# BACKUP_POWER.net
KiCad netlist of a schematic drawn in Altium Designer
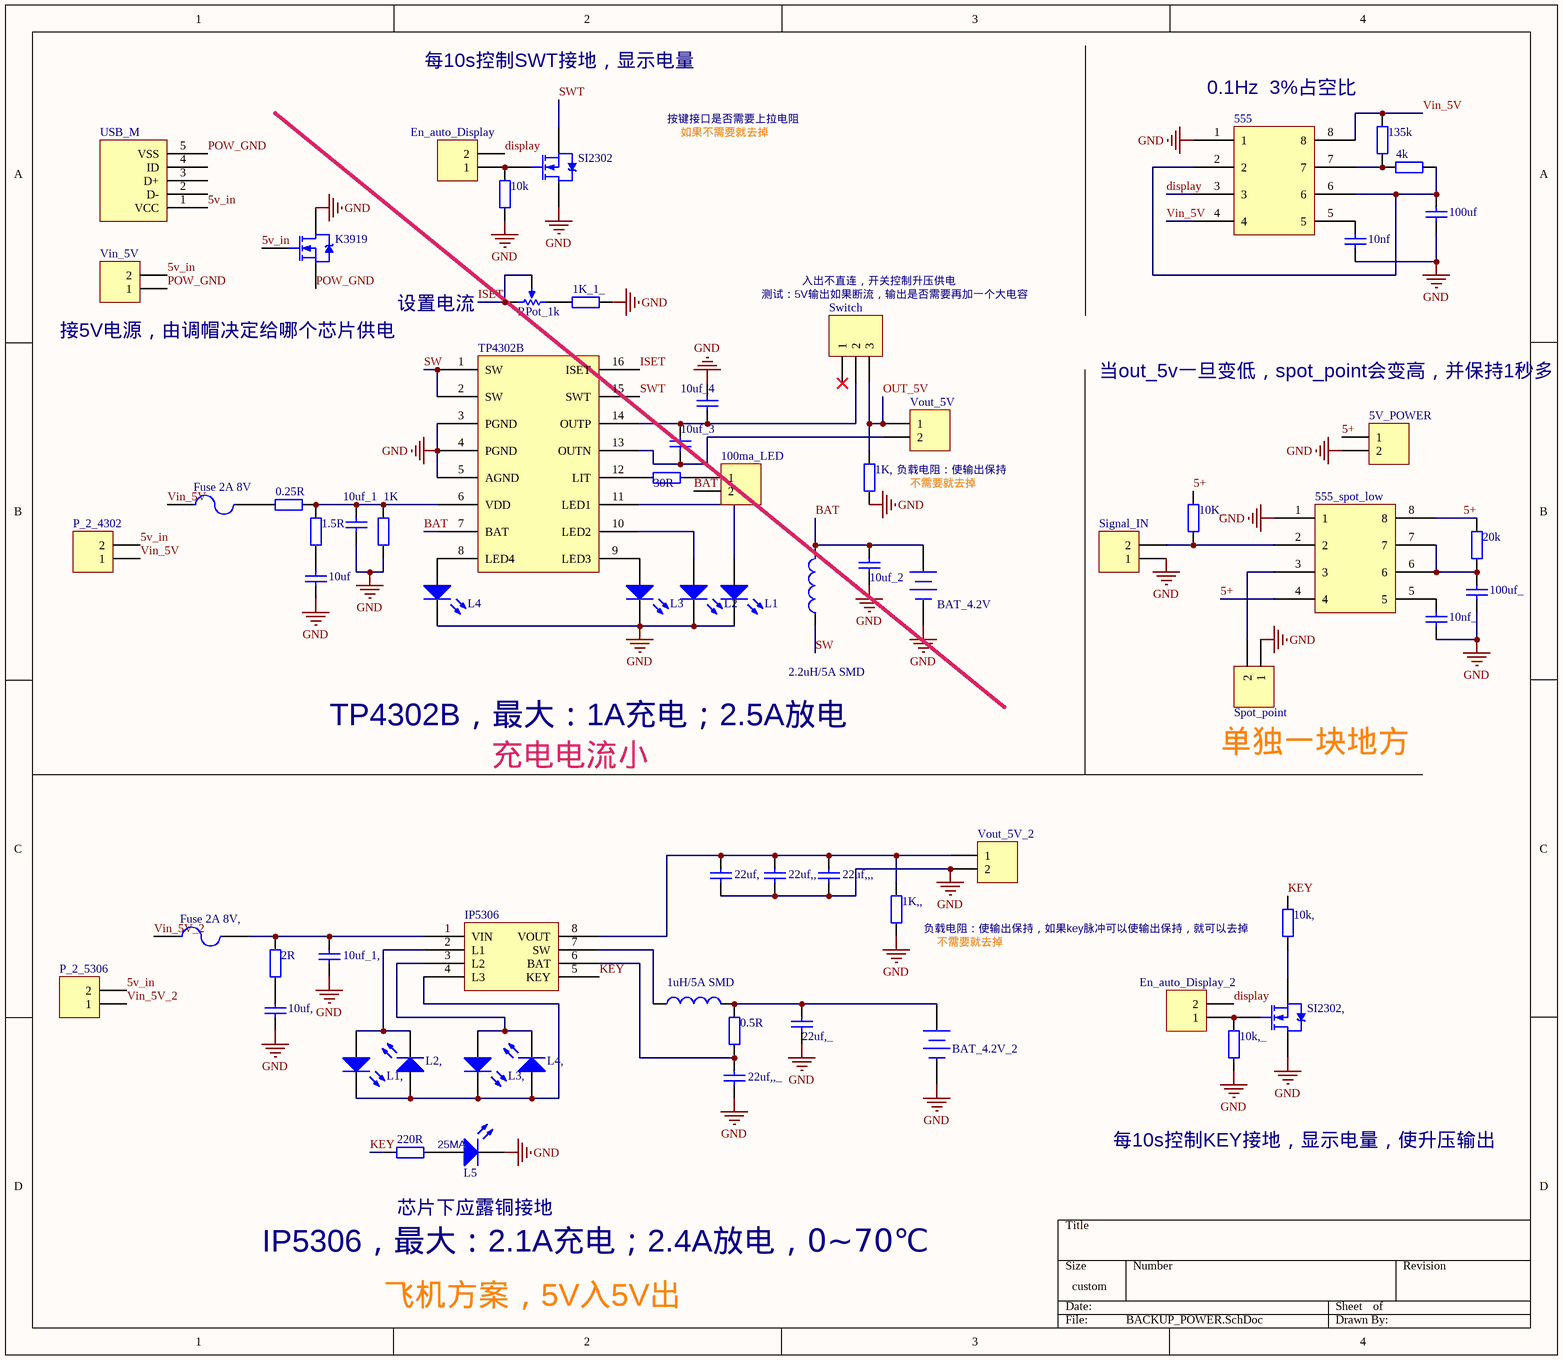
[diagram p0: BACKUP_POWER.SchDoc]

(export (version "E")
  (design (tool "Eeschema 10.0.6"))
  (components
    (comp (ref "0.5R")
      (value "Res2")
      (footprint "0805A")
      (description "Resistor")
      (fields (field (name "PUBLISHER") "Altium Limited"))
      (libsource (lib "") (part "Res2_2"))
    )
    (comp (ref "0.25R")
      (value "Res2")
      (footprint "1206")
      (description "Resistor")
      (fields (field (name "PUBLISHER") "Altium Limited"))
      (libsource (lib "Miscellaneous Devices") (part "Res2"))
    )
    (comp (ref "1.5R")
      (value "Res2")
      (footprint "0805A")
      (description "Resistor")
      (fields (field (name "PUBLISHER") "Altium Limited"))
      (libsource (lib "") (part "Res2_1"))
    )
    (comp (ref "1K")
      (value "Res2")
      (footprint "0805A")
      (description "Resistor")
      (fields (field (name "PUBLISHER") "Altium Limited"))
      (libsource (lib "") (part "Res2_1"))
    )
    (comp (ref "1K,")
      (value "Res2")
      (footprint "0805A")
      (description "Resistor")
      (fields (field (name "PUBLISHER") "Altium Limited"))
      (libsource (lib "") (part "Res2_1"))
    )
    (comp (ref "1K,,")
      (value "Res2")
      (footprint "0805A")
      (description "Resistor")
      (fields (field (name "PUBLISHER") "Altium Limited"))
      (libsource (lib "") (part "Res2_1"))
    )
    (comp (ref "1K_1_")
      (value "Res2")
      (footprint "0805A")
      (description "Resistor")
      (fields (field (name "PUBLISHER") "Altium Limited"))
      (libsource (lib "Miscellaneous Devices") (part "Res2"))
    )
    (comp (ref "1uH/5A SMD")
      (value "Inductor")
      (footprint "6 X 6-L")
      (fields (field (name "PUBLISHER") "Altium Limited"))
      (libsource (lib "Miscellaneous Devices") (part "Inductor"))
    )
    (comp (ref "2.2uH/5A SMD")
      (value "Inductor")
      (footprint "6 X 6-L")
      (fields (field (name "PUBLISHER") "Altium Limited"))
      (libsource (lib "Miscellaneous Devices") (part "Inductor"))
    )
    (comp (ref "2R")
      (value "Res2")
      (footprint "0805A")
      (description "Resistor")
      (fields (field (name "PUBLISHER") "Altium Limited"))
      (libsource (lib "") (part "Res2_1"))
    )
    (comp (ref "4k")
      (value "Res2")
      (footprint "0805A")
      (description "Resistor")
      (fields (field (name "PUBLISHER") "Altium Limited"))
      (libsource (lib "Miscellaneous Devices") (part "Res2"))
    )
    (comp (ref "5V_POWER")
      (value "Header 2")
      (footprint "HDR1X2")
      (description "Header, 2-Pin")
      (fields (field (name "PUBLISHER") "Altium Limited"))
      (libsource (lib "") (part "Header 2_1"))
    )
    (comp (ref "10k")
      (value "Res2")
      (footprint "0805A")
      (description "Resistor")
      (fields (field (name "PUBLISHER") "Altium Limited"))
      (libsource (lib "") (part "Res2_2"))
    )
    (comp (ref "10k,")
      (value "Res2")
      (footprint "0805A")
      (description "Resistor")
      (fields (field (name "PUBLISHER") "Altium Limited"))
      (libsource (lib "") (part "Res2_2"))
    )
    (comp (ref "10k,_")
      (value "Res2")
      (footprint "0805A")
      (description "Resistor")
      (fields (field (name "PUBLISHER") "Altium Limited"))
      (libsource (lib "") (part "Res2_2"))
    )
    (comp (ref "10K_")
      (value "Res2")
      (footprint "0805A")
      (description "Resistor")
      (fields (field (name "PUBLISHER") "Altium Limited"))
      (libsource (lib "") (part "Res2_1"))
    )
    (comp (ref "10nf")
      (value "Cap")
      (footprint "C-RAD-0805")
      (description "Capacitor")
      (fields (field (name "PUBLISHER") "Altium Limited"))
      (libsource (lib "Miscellaneous Devices") (part "Cap"))
    )
    (comp (ref "10nf_")
      (value "Cap")
      (footprint "C-RAD-0805")
      (description "Capacitor")
      (fields (field (name "PUBLISHER") "Altium Limited"))
      (libsource (lib "Miscellaneous Devices") (part "Cap"))
    )
    (comp (ref "10uf")
      (value "Cap")
      (footprint "C-RAD-0805")
      (description "Capacitor")
      (fields (field (name "PUBLISHER") "Altium Limited"))
      (libsource (lib "Miscellaneous Devices") (part "Cap"))
    )
    (comp (ref "10uf,")
      (value "Cap")
      (footprint "C-RAD-0805")
      (description "Capacitor")
      (fields (field (name "PUBLISHER") "Altium Limited"))
      (libsource (lib "Miscellaneous Devices") (part "Cap"))
    )
    (comp (ref "10uf_1")
      (value "Cap")
      (footprint "C-RAD-0805")
      (description "Capacitor")
      (fields (field (name "PUBLISHER") "Altium Limited"))
      (libsource (lib "Miscellaneous Devices") (part "Cap"))
    )
    (comp (ref "10uf_1,")
      (value "Cap")
      (footprint "C-RAD-0805")
      (description "Capacitor")
      (fields (field (name "PUBLISHER") "Altium Limited"))
      (libsource (lib "Miscellaneous Devices") (part "Cap"))
    )
    (comp (ref "10uf_2")
      (value "Cap")
      (footprint "C-RAD-0805")
      (description "Capacitor")
      (fields (field (name "PUBLISHER") "Altium Limited"))
      (libsource (lib "Miscellaneous Devices") (part "Cap"))
    )
    (comp (ref "10uf_3")
      (value "Cap")
      (footprint "C-RAD-0805")
      (description "Capacitor")
      (fields (field (name "PUBLISHER") "Altium Limited"))
      (libsource (lib "Miscellaneous Devices") (part "Cap"))
    )
    (comp (ref "10uf_4")
      (value "Cap")
      (footprint "C-RAD-0805")
      (description "Capacitor")
      (fields (field (name "PUBLISHER") "Altium Limited"))
      (libsource (lib "Miscellaneous Devices") (part "Cap"))
    )
    (comp (ref "20k")
      (value "Res2")
      (footprint "0805A")
      (description "Resistor")
      (fields (field (name "PUBLISHER") "Altium Limited"))
      (libsource (lib "") (part "Res2_1"))
    )
    (comp (ref "22uf,")
      (value "Cap")
      (footprint "C-RAD-0805")
      (description "Capacitor")
      (fields (field (name "PUBLISHER") "Altium Limited"))
      (libsource (lib "Miscellaneous Devices") (part "Cap"))
    )
    (comp (ref "22uf,,")
      (value "Cap")
      (footprint "C-RAD-0805")
      (description "Capacitor")
      (fields (field (name "PUBLISHER") "Altium Limited"))
      (libsource (lib "Miscellaneous Devices") (part "Cap"))
    )
    (comp (ref "22uf,,,")
      (value "Cap")
      (footprint "C-RAD-0805")
      (description "Capacitor")
      (fields (field (name "PUBLISHER") "Altium Limited"))
      (libsource (lib "Miscellaneous Devices") (part "Cap"))
    )
    (comp (ref "22uf,,_")
      (value "Cap")
      (footprint "C-RAD-0805")
      (description "Capacitor")
      (fields (field (name "PUBLISHER") "Altium Limited"))
      (libsource (lib "Miscellaneous Devices") (part "Cap"))
    )
    (comp (ref "22uf,_")
      (value "Cap")
      (footprint "C-RAD-0805")
      (description "Capacitor")
      (fields (field (name "PUBLISHER") "Altium Limited"))
      (libsource (lib "Miscellaneous Devices") (part "Cap"))
    )
    (comp (ref "30R")
      (value "Res2")
      (footprint "0805A")
      (description "Resistor")
      (fields (field (name "PUBLISHER") "Altium Limited"))
      (libsource (lib "Miscellaneous Devices") (part "Res2"))
    )
    (comp (ref "100ma_LED")
      (value "Header 2")
      (footprint "HDR1X2")
      (description "Header, 2-Pin")
      (fields (field (name "PUBLISHER") "Altium Limited"))
      (libsource (lib "") (part "Header 2_1"))
    )
    (comp (ref "100uf")
      (value "Cap")
      (footprint "C-RAD-0805")
      (description "Capacitor")
      (fields (field (name "PUBLISHER") "Altium Limited"))
      (libsource (lib "Miscellaneous Devices") (part "Cap"))
    )
    (comp (ref "100uf_")
      (value "Cap")
      (footprint "C-RAD-0805")
      (description "Capacitor")
      (fields (field (name "PUBLISHER") "Altium Limited"))
      (libsource (lib "Miscellaneous Devices") (part "Cap"))
    )
    (comp (ref "135k")
      (value "Res2")
      (footprint "0805A")
      (description "Resistor")
      (fields (field (name "PUBLISHER") "Altium Limited"))
      (libsource (lib "") (part "Res2_2"))
    )
    (comp (ref "220R")
      (value "Res2")
      (footprint "0805A")
      (description "Resistor")
      (fields (field (name "PUBLISHER") "Altium Limited"))
      (libsource (lib "Miscellaneous Devices") (part "Res2"))
    )
    (comp (ref "555") (value "~") (footprint "SOP8") (libsource (lib "集成块") (part "555")))
    (comp (ref "555_spot_low") (value "~") (footprint "SOP8") (libsource (lib "集成块") (part "555")))
    (comp (ref "BAT_4.2V") (value "B") (footprint "HDR1X2") (libsource (lib "原理图封装库") (part "BAT")))
    (comp (ref "BAT_4.2V_2") (value "B") (footprint "HDR1X2") (libsource (lib "原理图封装库") (part "BAT")))
    (comp (ref "En_auto_Display")
      (value "Header 2")
      (footprint "HDR1X2")
      (description "Header, 2-Pin")
      (fields (field (name "PUBLISHER") "Altium Limited"))
      (libsource (lib "Miscellaneous Connectors") (part "Header 2"))
    )
    (comp (ref "En_auto_Display_2")
      (value "Header 2")
      (footprint "HDR1X2")
      (description "Header, 2-Pin")
      (fields (field (name "PUBLISHER") "Altium Limited"))
      (libsource (lib "Miscellaneous Connectors") (part "Header 2"))
    )
    (comp (ref "Fuse 2A 8V")
      (value "Fuse 2")
      (footprint "1812F")
      (description "Fuse")
      (fields (field (name "PUBLISHER") "Altium Limited"))
      (libsource (lib "Miscellaneous Devices") (part "Fuse 2"))
    )
    (comp (ref "Fuse 2A 8V,")
      (value "Fuse 2")
      (footprint "1812F")
      (description "Fuse")
      (fields (field (name "PUBLISHER") "Altium Limited"))
      (libsource (lib "Miscellaneous Devices") (part "Fuse 2"))
    )
    (comp (ref "IP5306") (value "~") (footprint "SOP8") (libsource (lib "电源管理") (part "IP5306")))
    (comp (ref "K3919")
      (value "LR7843")
      (footprint "MISCEPCB:TO-252")
      (description "N-Channel Power MOSFET")
      (fields (field (name "PUBLISHER") "Altium Limited"))
      (libsource (lib "Miscellaneous Devices") (part "NMOS-2"))
    )
    (comp (ref "L1")
      (value "LED0")
      (footprint "LED_0805")
      (description "发光二极管")
      (fields (field (name "PUBLISHER") "Altium Limited"))
      (libsource (lib "Fszhang") (part "LED0"))
    )
    (comp (ref "L1,")
      (value "LED0")
      (footprint "LED_0805")
      (description "发光二极管")
      (fields (field (name "PUBLISHER") "Altium Limited"))
      (libsource (lib "Fszhang") (part "LED0"))
    )
    (comp (ref "L2")
      (value "LED0")
      (footprint "LED_0805")
      (description "发光二极管")
      (fields (field (name "PUBLISHER") "Altium Limited"))
      (libsource (lib "Fszhang") (part "LED0"))
    )
    (comp (ref "L2,")
      (value "LED0")
      (footprint "LED_0805")
      (description "发光二极管")
      (fields (field (name "PUBLISHER") "Altium Limited"))
      (libsource (lib "Fszhang") (part "LED0"))
    )
    (comp (ref "L3")
      (value "LED0")
      (footprint "LED_0805")
      (description "发光二极管")
      (fields (field (name "PUBLISHER") "Altium Limited"))
      (libsource (lib "Fszhang") (part "LED0"))
    )
    (comp (ref "L3,")
      (value "LED0")
      (footprint "LED_0805")
      (description "发光二极管")
      (fields (field (name "PUBLISHER") "Altium Limited"))
      (libsource (lib "Fszhang") (part "LED0"))
    )
    (comp (ref "L4")
      (value "LED0")
      (footprint "LED_0805")
      (description "发光二极管")
      (fields (field (name "PUBLISHER") "Altium Limited"))
      (libsource (lib "Fszhang") (part "LED0"))
    )
    (comp (ref "L4,")
      (value "LED0")
      (footprint "LED_0805")
      (description "发光二极管")
      (fields (field (name "PUBLISHER") "Altium Limited"))
      (libsource (lib "Fszhang") (part "LED0"))
    )
    (comp (ref "L5")
      (value "LED0")
      (footprint "LED_0805")
      (description "发光二极管")
      (fields (field (name "PUBLISHER") "Altium Limited"))
      (libsource (lib "Fszhang") (part "LED0"))
    )
    (comp (ref "P_2_4302")
      (value "Header 2")
      (footprint "HDR1X2")
      (description "Header, 2-Pin")
      (fields (field (name "PUBLISHER") "Altium Limited"))
      (libsource (lib "Miscellaneous Connectors") (part "Header 2"))
    )
    (comp (ref "P_2_5306")
      (value "Header 2")
      (footprint "HDR1X2")
      (description "Header, 2-Pin")
      (fields (field (name "PUBLISHER") "Altium Limited"))
      (libsource (lib "Miscellaneous Connectors") (part "Header 2"))
    )
    (comp (ref "RPot_1k")
      (value "RPot")
      (footprint "VR_A1")
      (description "精密可调电阻")
      (fields (field (name "PUBLISHER") "Altium Limited"))
      (libsource (lib "Fszhang") (part "RPot"))
    )
    (comp (ref "SI2302")
      (value "LR7843")
      (footprint "SOT-23")
      (description "N-Channel Power MOSFET")
      (fields (field (name "PUBLISHER") "Altium Limited"))
      (libsource (lib "Miscellaneous Devices") (part "NMOS-2"))
    )
    (comp (ref "SI2302,")
      (value "LR7843")
      (footprint "SOT-23")
      (description "N-Channel Power MOSFET")
      (fields (field (name "PUBLISHER") "Altium Limited"))
      (libsource (lib "Miscellaneous Devices") (part "NMOS-2"))
    )
    (comp (ref "Signal_IN")
      (value "Header 2")
      (footprint "HDR1X2")
      (description "Header, 2-Pin")
      (fields (field (name "PUBLISHER") "Altium Limited"))
      (libsource (lib "Miscellaneous Connectors") (part "Header 2"))
    )
    (comp (ref "Spot_point")
      (value "Header 2")
      (footprint "HDR1X2")
      (description "Header, 2-Pin")
      (fields (field (name "PUBLISHER") "Altium Limited"))
      (libsource (lib "") (part "Header 2_2"))
    )
    (comp (ref "Switch")
      (value "Header 3")
      (footprint "SWITCH_A1")
      (description "Header, 3-Pin")
      (fields (field (name "PUBLISHER") "Altium Limited"))
      (libsource (lib "Miscellaneous Connectors") (part "Header 3"))
    )
    (comp (ref "TP4302B") (value "~") (footprint "SOP16") (libsource (lib "电源管理") (part "TP4302")))
    (comp (ref "USB_M")
      (value "USB_M")
      (footprint "USB_MICRO")
      (description "MicroUSB接口")
      (libsource (lib "Fszhang") (part "USB_M"))
    )
    (comp (ref "Vin_5V")
      (value "Header 2")
      (footprint "HDR1X2")
      (description "Header, 2-Pin")
      (fields (field (name "PUBLISHER") "Altium Limited"))
      (libsource (lib "Miscellaneous Connectors") (part "Header 2"))
    )
    (comp (ref "Vout_5V")
      (value "Header 2")
      (footprint "HDR1X2")
      (description "Header, 2-Pin")
      (fields (field (name "PUBLISHER") "Altium Limited"))
      (libsource (lib "") (part "Header 2_1"))
    )
    (comp (ref "Vout_5V_2")
      (value "Header 2")
      (footprint "HDR1X2")
      (description "Header, 2-Pin")
      (fields (field (name "PUBLISHER") "Altium Limited"))
      (libsource (lib "") (part "Header 2_1"))
    )
  )
  (nets
    (net (code "1") (name "/5+") (class "Default")
      (node (ref "10K_") (pin "2") (pinfunction "2_2") (pintype "passive"))
      (node (ref "20k") (pin "2") (pinfunction "2_2") (pintype "passive"))
      (node (ref "555_spot_low") (pin "4") (pinfunction "4_4") (pintype "passive"))
      (node (ref "555_spot_low") (pin "8") (pinfunction "8_8") (pintype "passive"))
      (node (ref "5V_POWER") (pin "1") (pinfunction "1_1") (pintype "passive"))
    )
    (net (code "2") (name "/5v_in") (class "Default")
      (node (ref "K3919") (pin "1") (pinfunction "G_1") (pintype "passive"))
      (node (ref "P_2_4302") (pin "2") (pinfunction "2_2") (pintype "passive"))
      (node (ref "P_2_5306") (pin "2") (pinfunction "2_2") (pintype "passive"))
      (node (ref "USB_M") (pin "1") (pinfunction "VCC_1") (pintype "passive"))
      (node (ref "Vin_5V") (pin "2") (pinfunction "2_2") (pintype "passive"))
    )
    (net (code "3") (name "/BAT") (class "Default")
      (node (ref "100ma_LED") (pin "2") (pinfunction "2_2") (pintype "passive"))
      (node (ref "10uf_2") (pin "1") (pinfunction "1_1") (pintype "passive"))
      (node (ref "2.2uH/5A SMD") (pin "2") (pinfunction "2_2") (pintype "passive"))
      (node (ref "BAT_4.2V") (pin "1") (pinfunction "+_1") (pintype "passive"))
      (node (ref "TP4302B") (pin "7") (pinfunction "BAT_7") (pintype "passive"))
    )
    (net (code "4") (name "/ISET") (class "Default")
      (node (ref "RPot_1k") (pin "2") (pinfunction "TAP_2") (pintype "passive"))
      (node (ref "RPot_1k") (pin "3") (pinfunction "BOT_3") (pintype "passive"))
      (node (ref "TP4302B") (pin "16") (pinfunction "ISET_16") (pintype "passive"))
    )
    (net (code "5") (name "/KEY") (class "Default")
      (node (ref "10k,") (pin "1") (pinfunction "1_1") (pintype "passive"))
      (node (ref "220R") (pin "2") (pinfunction "2_2") (pintype "passive"))
      (node (ref "IP5306") (pin "5") (pinfunction "KEY_5") (pintype "passive"))
    )
    (net (code "6") (name "/OUT_5V") (class "Default")
      (node (ref "1K,") (pin "2") (pinfunction "2_2") (pintype "passive"))
      (node (ref "Switch") (pin "3") (pinfunction "3_3") (pintype "passive"))
      (node (ref "Vout_5V") (pin "1") (pinfunction "1_1") (pintype "passive"))
    )
    (net (code "7") (name "/POW_GND") (class "Default")
      (node (ref "K3919") (pin "3") (pinfunction "S_3") (pintype "passive"))
      (node (ref "USB_M") (pin "5") (pinfunction "VSS_5") (pintype "passive"))
      (node (ref "Vin_5V") (pin "1") (pinfunction "1_1") (pintype "passive"))
    )
    (net (code "8") (name "/SW") (class "Default")
      (node (ref "2.2uH/5A SMD") (pin "1") (pinfunction "1_1") (pintype "passive"))
      (node (ref "TP4302B") (pin "1") (pinfunction "SW_1") (pintype "passive"))
      (node (ref "TP4302B") (pin "2") (pinfunction "SW_2") (pintype "passive"))
    )
    (net (code "9") (name "/SWT") (class "Default")
      (node (ref "SI2302") (pin "3") (pinfunction "S_3") (pintype "passive"))
      (node (ref "TP4302B") (pin "15") (pinfunction "SWT_15") (pintype "passive"))
    )
    (net (code "10") (name "/Vin_5V") (class "Default")
      (node (ref "135k") (pin "1") (pinfunction "1_1") (pintype "passive"))
      (node (ref "555") (pin "4") (pinfunction "4_4") (pintype "passive"))
      (node (ref "555") (pin "8") (pinfunction "8_8") (pintype "passive"))
      (node (ref "Fuse 2A 8V") (pin "1") (pinfunction "1_1") (pintype "passive"))
      (node (ref "P_2_4302") (pin "1") (pinfunction "1_1") (pintype "passive"))
    )
    (net (code "11") (name "/Vin_5V_2") (class "Default")
      (node (ref "Fuse 2A 8V,") (pin "1") (pinfunction "1_1") (pintype "passive"))
      (node (ref "P_2_5306") (pin "1") (pinfunction "1_1") (pintype "passive"))
    )
    (net (code "12") (name "/display") (class "Default")
      (node (ref "555") (pin "3") (pinfunction "3_3") (pintype "passive"))
      (node (ref "En_auto_Display") (pin "2") (pinfunction "2_2") (pintype "passive"))
      (node (ref "En_auto_Display_2") (pin "2") (pinfunction "2_2") (pintype "passive"))
    )
    (net (code "13") (name "GND") (class "Default")
      (node (ref "100uf") (pin "1") (pinfunction "1_1") (pintype "passive"))
      (node (ref "100uf_") (pin "1") (pinfunction "1_1") (pintype "passive"))
      (node (ref "10k") (pin "2") (pinfunction "2_2") (pintype "passive"))
      (node (ref "10k,_") (pin "2") (pinfunction "2_2") (pintype "passive"))
      (node (ref "10nf") (pin "1") (pinfunction "1_1") (pintype "passive"))
      (node (ref "10nf_") (pin "1") (pinfunction "1_1") (pintype "passive"))
      (node (ref "10uf") (pin "2") (pinfunction "2_2") (pintype "passive"))
      (node (ref "10uf,") (pin "2") (pinfunction "2_2") (pintype "passive"))
      (node (ref "10uf_1") (pin "2") (pinfunction "2_2") (pintype "passive"))
      (node (ref "10uf_1,") (pin "2") (pinfunction "2_2") (pintype "passive"))
      (node (ref "10uf_2") (pin "2") (pinfunction "2_2") (pintype "passive"))
      (node (ref "10uf_4") (pin "2") (pinfunction "2_2") (pintype "passive"))
      (node (ref "1K") (pin "1") (pinfunction "1_1") (pintype "passive"))
      (node (ref "1K,") (pin "1") (pinfunction "1_1") (pintype "passive"))
      (node (ref "1K,,") (pin "1") (pinfunction "1_1") (pintype "passive"))
      (node (ref "1K_1_") (pin "1") (pinfunction "1_1") (pintype "passive"))
      (node (ref "22uf,") (pin "2") (pinfunction "2_2") (pintype "passive"))
      (node (ref "22uf,,") (pin "2") (pinfunction "2_2") (pintype "passive"))
      (node (ref "22uf,,,") (pin "2") (pinfunction "2_2") (pintype "passive"))
      (node (ref "22uf,,_") (pin "2") (pinfunction "2_2") (pintype "passive"))
      (node (ref "22uf,_") (pin "2") (pinfunction "2_2") (pintype "passive"))
      (node (ref "555") (pin "1") (pinfunction "1_1") (pintype "passive"))
      (node (ref "555_spot_low") (pin "1") (pinfunction "1_1") (pintype "passive"))
      (node (ref "5V_POWER") (pin "2") (pinfunction "2_2") (pintype "passive"))
      (node (ref "BAT_4.2V") (pin "2") (pinfunction "-_2") (pintype "passive"))
      (node (ref "BAT_4.2V_2") (pin "2") (pinfunction "-_2") (pintype "passive"))
      (node (ref "K3919") (pin "2") (pinfunction "D_2") (pintype "passive"))
      (node (ref "L1") (pin "2") (pinfunction "K_2") (pintype "passive"))
      (node (ref "L2") (pin "2") (pinfunction "K_2") (pintype "passive"))
      (node (ref "L3") (pin "2") (pinfunction "K_2") (pintype "passive"))
      (node (ref "L4") (pin "2") (pinfunction "K_2") (pintype "passive"))
      (node (ref "L5") (pin "2") (pinfunction "K_2") (pintype "passive"))
      (node (ref "SI2302") (pin "2") (pinfunction "D_2") (pintype "passive"))
      (node (ref "SI2302,") (pin "2") (pinfunction "D_2") (pintype "passive"))
      (node (ref "Signal_IN") (pin "1") (pinfunction "1_1") (pintype "passive"))
      (node (ref "Spot_point") (pin "1") (pinfunction "1_1") (pintype "passive"))
      (node (ref "TP4302B") (pin "3") (pinfunction "PGND_3") (pintype "passive"))
      (node (ref "TP4302B") (pin "4") (pinfunction "PGND_4") (pintype "passive"))
      (node (ref "TP4302B") (pin "5") (pinfunction "AGND_5") (pintype "passive"))
      (node (ref "Vout_5V_2") (pin "2") (pinfunction "2_2") (pintype "passive"))
    )
    (net (code "14") (name "Net-(0.25R-Pad2)") (class "Default")
      (node (ref "0.25R") (pin "2") (pinfunction "2_2") (pintype "passive"))
      (node (ref "Fuse 2A 8V") (pin "2") (pinfunction "2_2") (pintype "passive"))
    )
    (net (code "15") (name "Net-(1.5R-Pad1)") (class "Default")
      (node (ref "1.5R") (pin "1") (pinfunction "1_1") (pintype "passive"))
      (node (ref "10uf") (pin "1") (pinfunction "1_1") (pintype "passive"))
    )
    (net (code "16") (name "Net-(10K_-Pad1)") (class "Default")
      (node (ref "10K_") (pin "1") (pinfunction "1_1") (pintype "passive"))
      (node (ref "555_spot_low") (pin "2") (pinfunction "2_2") (pintype "passive"))
      (node (ref "Signal_IN") (pin "2") (pinfunction "2_2") (pintype "passive"))
    )
    (net (code "17") (name "Net-(10nf-Pad2)") (class "Default")
      (node (ref "10nf") (pin "2") (pinfunction "2_2") (pintype "passive"))
      (node (ref "555") (pin "5") (pinfunction "5_5") (pintype "passive"))
    )
    (net (code "18") (name "Net-(10nf_-Pad2)") (class "Default")
      (node (ref "10nf_") (pin "2") (pinfunction "2_2") (pintype "passive"))
      (node (ref "555_spot_low") (pin "5") (pinfunction "5_5") (pintype "passive"))
    )
    (net (code "19") (name "Net-(10uf,-Pad1)") (class "Default")
      (node (ref "10uf,") (pin "1") (pinfunction "1_1") (pintype "passive"))
      (node (ref "2R") (pin "1") (pinfunction "1_1") (pintype "passive"))
    )
    (net (code "20") (name "Net-(100ma_LED-Pad1)") (class "Default")
      (node (ref "100ma_LED") (pin "1") (pinfunction "1_1") (pintype "passive"))
      (node (ref "30R") (pin "1") (pinfunction "1_1") (pintype "passive"))
    )
    (net (code "21") (name "Net-(100uf-Pad2)") (class "Default")
      (node (ref "100uf") (pin "2") (pinfunction "2_2") (pintype "passive"))
      (node (ref "4k") (pin "1") (pinfunction "1_1") (pintype "passive"))
      (node (ref "555") (pin "2") (pinfunction "2_2") (pintype "passive"))
      (node (ref "555") (pin "6") (pinfunction "6_6") (pintype "passive"))
    )
    (net (code "22") (name "Net-(100uf_-Pad2)") (class "Default")
      (node (ref "100uf_") (pin "2") (pinfunction "2_2") (pintype "passive"))
      (node (ref "20k") (pin "1") (pinfunction "1_1") (pintype "passive"))
      (node (ref "555_spot_low") (pin "6") (pinfunction "6_6") (pintype "passive"))
      (node (ref "555_spot_low") (pin "7") (pinfunction "7_7") (pintype "passive"))
    )
    (net (code "23") (name "Net-(135k-Pad2)") (class "Default")
      (node (ref "135k") (pin "2") (pinfunction "2_2") (pintype "passive"))
      (node (ref "4k") (pin "2") (pinfunction "2_2") (pintype "passive"))
      (node (ref "555") (pin "7") (pinfunction "7_7") (pintype "passive"))
    )
    (net (code "24") (name "Net-(555_spot_low-Pad3)") (class "Default")
      (node (ref "555_spot_low") (pin "3") (pinfunction "3_3") (pintype "passive"))
      (node (ref "Spot_point") (pin "2") (pinfunction "2_2") (pintype "passive"))
    )
    (net (code "25") (name "Net-(BAT_4.2V_2-+)") (class "Default")
      (node (ref "0.5R") (pin "1") (pinfunction "1_1") (pintype "passive"))
      (node (ref "1uH/5A SMD") (pin "2") (pinfunction "2_2") (pintype "passive"))
      (node (ref "22uf,_") (pin "1") (pinfunction "1_1") (pintype "passive"))
      (node (ref "BAT_4.2V_2") (pin "1") (pinfunction "+_1") (pintype "passive"))
    )
    (net (code "26") (name "Net-(IP5306-BAT)") (class "Default")
      (node (ref "0.5R") (pin "2") (pinfunction "2_2") (pintype "passive"))
      (node (ref "22uf,,_") (pin "1") (pinfunction "1_1") (pintype "passive"))
      (node (ref "IP5306") (pin "6") (pinfunction "BAT_6") (pintype "passive"))
    )
    (net (code "27") (name "Net-(IP5306-L1)") (class "Default")
      (node (ref "IP5306") (pin "2") (pinfunction "L1_2") (pintype "passive"))
      (node (ref "L1,") (pin "1") (pinfunction "A_1") (pintype "passive"))
      (node (ref "L2,") (pin "2") (pinfunction "K_2") (pintype "passive"))
    )
    (net (code "28") (name "Net-(IP5306-L2)") (class "Default")
      (node (ref "IP5306") (pin "3") (pinfunction "L2_3") (pintype "passive"))
      (node (ref "L3,") (pin "1") (pinfunction "A_1") (pintype "passive"))
      (node (ref "L4,") (pin "2") (pinfunction "K_2") (pintype "passive"))
    )
    (net (code "29") (name "Net-(IP5306-L3)") (class "Default")
      (node (ref "IP5306") (pin "4") (pinfunction "L3_4") (pintype "passive"))
      (node (ref "L1,") (pin "2") (pinfunction "K_2") (pintype "passive"))
      (node (ref "L2,") (pin "1") (pinfunction "A_1") (pintype "passive"))
      (node (ref "L3,") (pin "2") (pinfunction "K_2") (pintype "passive"))
      (node (ref "L4,") (pin "1") (pinfunction "A_1") (pintype "passive"))
    )
    (net (code "30") (name "Net-(IP5306-SW)") (class "Default")
      (node (ref "1uH/5A SMD") (pin "1") (pinfunction "1_1") (pintype "passive"))
      (node (ref "IP5306") (pin "7") (pinfunction "SW_7") (pintype "passive"))
    )
    (net (code "31") (name "Net-(IP5306-VIN)") (class "Default")
      (node (ref "10uf_1,") (pin "1") (pinfunction "1_1") (pintype "passive"))
      (node (ref "2R") (pin "2") (pinfunction "2_2") (pintype "passive"))
      (node (ref "Fuse 2A 8V,") (pin "2") (pinfunction "2_2") (pintype "passive"))
      (node (ref "IP5306") (pin "1") (pinfunction "VIN_1") (pintype "passive"))
    )
    (net (code "32") (name "Net-(IP5306-VOUT)") (class "Default")
      (node (ref "1K,,") (pin "2") (pinfunction "2_2") (pintype "passive"))
      (node (ref "22uf,") (pin "1") (pinfunction "1_1") (pintype "passive"))
      (node (ref "22uf,,") (pin "1") (pinfunction "1_1") (pintype "passive"))
      (node (ref "22uf,,,") (pin "1") (pinfunction "1_1") (pintype "passive"))
      (node (ref "IP5306") (pin "8") (pinfunction "VOUT_8") (pintype "passive"))
      (node (ref "Vout_5V_2") (pin "1") (pinfunction "1_1") (pintype "passive"))
    )
    (net (code "33") (name "Net-(L1-A)") (class "Default")
      (node (ref "L1") (pin "1") (pinfunction "A_1") (pintype "passive"))
      (node (ref "TP4302B") (pin "11") (pinfunction "LED1_11") (pintype "passive"))
    )
    (net (code "34") (name "Net-(L2-A)") (class "Default")
      (node (ref "L2") (pin "1") (pinfunction "A_1") (pintype "passive"))
      (node (ref "TP4302B") (pin "10") (pinfunction "LED2_10") (pintype "passive"))
    )
    (net (code "35") (name "Net-(L3-A)") (class "Default")
      (node (ref "L3") (pin "1") (pinfunction "A_1") (pintype "passive"))
      (node (ref "TP4302B") (pin "9") (pinfunction "LED3_9") (pintype "passive"))
    )
    (net (code "36") (name "Net-(L4-A)") (class "Default")
      (node (ref "L4") (pin "1") (pinfunction "A_1") (pintype "passive"))
      (node (ref "TP4302B") (pin "8") (pinfunction "LED4_8") (pintype "passive"))
    )
    (net (code "37") (name "Net-(L5-A)") (class "Default")
      (node (ref "220R") (pin "1") (pinfunction "1_1") (pintype "passive"))
      (node (ref "L5") (pin "1") (pinfunction "A_1") (pintype "passive"))
    )
    (net (code "38") (name "Net-(RPot_1k-TOP)") (class "Default")
      (node (ref "1K_1_") (pin "2") (pinfunction "2_2") (pintype "passive"))
      (node (ref "RPot_1k") (pin "1") (pinfunction "TOP_1") (pintype "passive"))
    )
    (net (code "39") (name "Net-(SI2302,-G)") (class "Default")
      (node (ref "10k,_") (pin "1") (pinfunction "1_1") (pintype "passive"))
      (node (ref "En_auto_Display_2") (pin "1") (pinfunction "1_1") (pintype "passive"))
      (node (ref "SI2302,") (pin "1") (pinfunction "G_1") (pintype "passive"))
    )
    (net (code "40") (name "Net-(SI2302,-S)") (class "Default")
      (node (ref "10k,") (pin "2") (pinfunction "2_2") (pintype "passive"))
      (node (ref "SI2302,") (pin "3") (pinfunction "S_3") (pintype "passive"))
    )
    (net (code "41") (name "Net-(SI2302-G)") (class "Default")
      (node (ref "10k") (pin "1") (pinfunction "1_1") (pintype "passive"))
      (node (ref "En_auto_Display") (pin "1") (pinfunction "1_1") (pintype "passive"))
      (node (ref "SI2302") (pin "1") (pinfunction "G_1") (pintype "passive"))
    )
    (net (code "42") (name "Net-(TP4302B-LIT)") (class "Default")
      (node (ref "30R") (pin "2") (pinfunction "2_2") (pintype "passive"))
      (node (ref "TP4302B") (pin "12") (pinfunction "LIT_12") (pintype "passive"))
    )
    (net (code "43") (name "Net-(TP4302B-OUTN)") (class "Default")
      (node (ref "10uf_3") (pin "2") (pinfunction "2_2") (pintype "passive"))
      (node (ref "TP4302B") (pin "13") (pinfunction "OUTN_13") (pintype "passive"))
      (node (ref "Vout_5V") (pin "2") (pinfunction "2_2") (pintype "passive"))
    )
    (net (code "44") (name "Net-(TP4302B-OUTP)") (class "Default")
      (node (ref "10uf_3") (pin "1") (pinfunction "1_1") (pintype "passive"))
      (node (ref "10uf_4") (pin "1") (pinfunction "1_1") (pintype "passive"))
      (node (ref "Switch") (pin "2") (pinfunction "2_2") (pintype "passive"))
      (node (ref "TP4302B") (pin "14") (pinfunction "OUTP_14") (pintype "passive"))
    )
    (net (code "45") (name "Net-(TP4302B-VDD)") (class "Default")
      (node (ref "0.25R") (pin "1") (pinfunction "1_1") (pintype "passive"))
      (node (ref "1.5R") (pin "2") (pinfunction "2_2") (pintype "passive"))
      (node (ref "10uf_1") (pin "1") (pinfunction "1_1") (pintype "passive"))
      (node (ref "1K") (pin "2") (pinfunction "2_2") (pintype "passive"))
      (node (ref "TP4302B") (pin "6") (pinfunction "VDD_6") (pintype "passive"))
    )
    (net (code "46") (name "unconnected-(Switch-Pad1)") (class "Default")
      (node (ref "Switch") (pin "1") (pinfunction "1_1") (pintype "passive+no_connect"))
    )
    (net (code "47") (name "unconnected-(USB_M-D+-Pad3)") (class "Default")
      (node (ref "USB_M") (pin "3") (pinfunction "D+_3") (pintype "passive"))
    )
    (net (code "48") (name "unconnected-(USB_M-D--Pad2)") (class "Default")
      (node (ref "USB_M") (pin "2") (pinfunction "D-_2") (pintype "passive"))
    )
    (net (code "49") (name "unconnected-(USB_M-ID-Pad4)") (class "Default")
      (node (ref "USB_M") (pin "4") (pinfunction "ID_4") (pintype "passive"))
    )
  )
)
